# basic.net
KiCad netlist of a schematic drawn in EAGLE
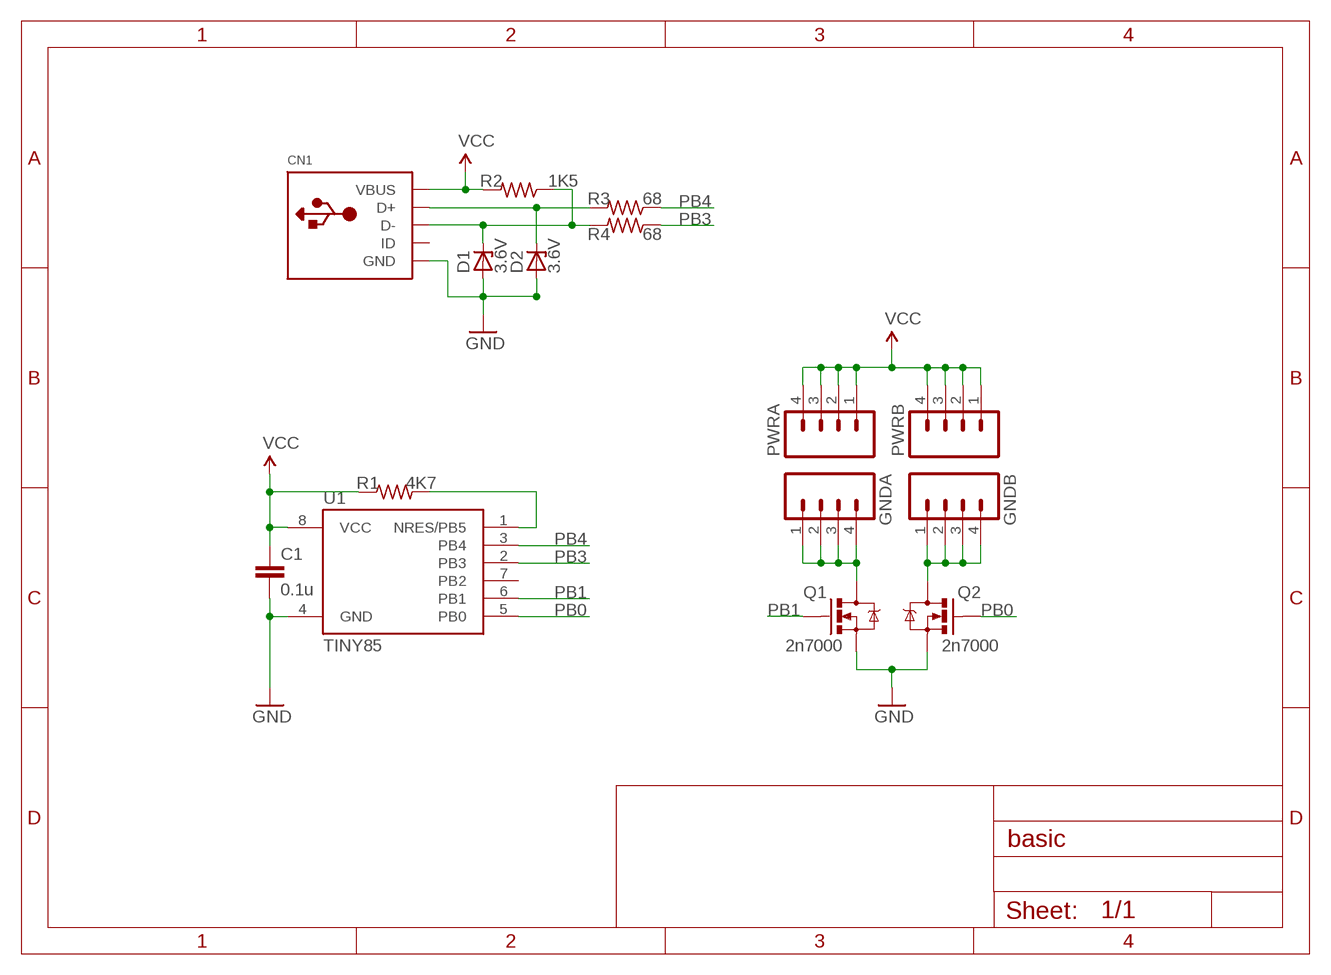
[diagram p0: schematic, sheet 1]

(export (version "E")
  (design (tool "Eeschema 10.0.6"))
  (components
    (comp (ref "C1")
      (value "0.1u")
      (footprint "eagle-import:C025-024X044")
      (libsource (lib "eagle-import") (part "C-EU025-024X044"))
    )
    (comp (ref "CN1")
      (value "USBMOLEX")
      (footprint "eagle-import:USB-MINIB-THM-MOLEX")
      (libsource (lib "eagle-import") (part "USBMOLEX"))
    )
    (comp (ref "D1")
      (value "3.6V")
      (footprint "eagle-import:ZDIO-5")
      (libsource (lib "eagle-import") (part "ZENER-DIODEZD-5"))
    )
    (comp (ref "D2")
      (value "3.6V")
      (footprint "eagle-import:ZDIO-5")
      (libsource (lib "eagle-import") (part "ZENER-DIODEZD-5"))
    )
    (comp (ref "GNDA")
      (value "M041X04_NO_SILK")
      (footprint "eagle-import:1X04_NO_SILK")
      (libsource (lib "eagle-import") (part "M041X04_NO_SILK"))
    )
    (comp (ref "GNDB")
      (value "M041X04_NO_SILK")
      (footprint "eagle-import:1X04_NO_SILK")
      (libsource (lib "eagle-import") (part "M041X04_NO_SILK"))
    )
    (comp (ref "PWRA")
      (value "M041X04_NO_SILK")
      (footprint "eagle-import:1X04_NO_SILK")
      (libsource (lib "eagle-import") (part "M041X04_NO_SILK"))
    )
    (comp (ref "PWRB")
      (value "M041X04_NO_SILK")
      (footprint "eagle-import:1X04_NO_SILK")
      (libsource (lib "eagle-import") (part "M041X04_NO_SILK"))
    )
    (comp (ref "Q1")
      (value "2n7000")
      (footprint "eagle-import:TO-92")
      (libsource (lib "eagle-import") (part "MOSFET-NCHANNEL2N7000"))
    )
    (comp (ref "Q2")
      (value "2n7000")
      (footprint "eagle-import:TO-92")
      (libsource (lib "eagle-import") (part "MOSFET-NCHANNEL2N7000"))
    )
    (comp (ref "R1")
      (value "4K7")
      (footprint "eagle-import:0204V")
      (libsource (lib "eagle-import") (part "R-US_0204/2V"))
    )
    (comp (ref "R2")
      (value "1K5")
      (footprint "eagle-import:0204V")
      (libsource (lib "eagle-import") (part "R-US_0204/2V"))
    )
    (comp (ref "R3")
      (value "68")
      (footprint "eagle-import:0204V")
      (libsource (lib "eagle-import") (part "R-US_0204/2V"))
    )
    (comp (ref "R4")
      (value "68")
      (footprint "eagle-import:0204V")
      (libsource (lib "eagle-import") (part "R-US_0204/2V"))
    )
    (comp (ref "U1")
      (value "TINY85")
      (footprint "eagle-import:PDIP08_300MIL")
      (libsource (lib "eagle-import") (part "ATTINY85P-20"))
    )
  )
  (nets
    (net (code "1") (name "/PB0") (class "Default")
      (node (ref "Q2") (pin "2") (pinfunction "G_2") (pintype "passive"))
      (node (ref "U1") (pin "5") (pinfunction "PB0_5") (pintype "bidirectional"))
    )
    (net (code "2") (name "/PB1") (class "Default")
      (node (ref "Q1") (pin "2") (pinfunction "G_2") (pintype "passive"))
      (node (ref "U1") (pin "6") (pinfunction "PB1_6") (pintype "bidirectional"))
    )
    (net (code "3") (name "/PB3") (class "Default")
      (node (ref "R4") (pin "1") (pinfunction "1_1") (pintype "passive"))
      (node (ref "U1") (pin "2") (pinfunction "PB3_2") (pintype "bidirectional"))
    )
    (net (code "4") (name "/PB4") (class "Default")
      (node (ref "R3") (pin "1") (pinfunction "1_1") (pintype "passive"))
      (node (ref "U1") (pin "3") (pinfunction "PB4_3") (pintype "bidirectional"))
    )
    (net (code "5") (name "GND") (class "Default")
      (node (ref "C1") (pin "2") (pinfunction "2_2") (pintype "passive"))
      (node (ref "CN1") (pin "GND") (pinfunction "GND_GND") (pintype "power_in"))
      (node (ref "D1") (pin "A") (pinfunction "A_A") (pintype "passive"))
      (node (ref "D2") (pin "A") (pinfunction "A_A") (pintype "passive"))
      (node (ref "Q1") (pin "1") (pinfunction "S_1") (pintype "passive"))
      (node (ref "Q2") (pin "1") (pinfunction "S_1") (pintype "passive"))
      (node (ref "U1") (pin "4") (pinfunction "GND_4") (pintype "power_in"))
    )
    (net (code "6") (name "Net-(CN1-PadD+)") (class "Default")
      (node (ref "CN1") (pin "D+") (pinfunction "D+_D+") (pintype "bidirectional"))
      (node (ref "D2") (pin "C") (pinfunction "C_C") (pintype "passive"))
      (node (ref "R3") (pin "2") (pinfunction "2_2") (pintype "passive"))
    )
    (net (code "7") (name "Net-(CN1-PadD-)") (class "Default")
      (node (ref "CN1") (pin "D-") (pinfunction "D-_D-") (pintype "bidirectional"))
      (node (ref "D1") (pin "C") (pinfunction "C_C") (pintype "passive"))
      (node (ref "R2") (pin "1") (pinfunction "1_1") (pintype "passive"))
      (node (ref "R4") (pin "2") (pinfunction "2_2") (pintype "passive"))
    )
    (net (code "8") (name "Net-(Q1-D)") (class "Default")
      (node (ref "GNDA") (pin "1") (pinfunction "1_1") (pintype "passive"))
      (node (ref "GNDA") (pin "2") (pinfunction "2_2") (pintype "passive"))
      (node (ref "GNDA") (pin "3") (pinfunction "3_3") (pintype "passive"))
      (node (ref "GNDA") (pin "4") (pinfunction "4_4") (pintype "passive"))
      (node (ref "Q1") (pin "3") (pinfunction "D_3") (pintype "passive"))
    )
    (net (code "9") (name "Net-(Q2-D)") (class "Default")
      (node (ref "GNDB") (pin "1") (pinfunction "1_1") (pintype "passive"))
      (node (ref "GNDB") (pin "2") (pinfunction "2_2") (pintype "passive"))
      (node (ref "GNDB") (pin "3") (pinfunction "3_3") (pintype "passive"))
      (node (ref "GNDB") (pin "4") (pinfunction "4_4") (pintype "passive"))
      (node (ref "Q2") (pin "3") (pinfunction "D_3") (pintype "passive"))
    )
    (net (code "10") (name "Net-(U1-NRES{slash}PB5)") (class "Default")
      (node (ref "R1") (pin "2") (pinfunction "2_2") (pintype "passive"))
      (node (ref "U1") (pin "1") (pinfunction "NRES/PB5_1") (pintype "bidirectional"))
    )
    (net (code "11") (name "VCC") (class "Default")
      (node (ref "C1") (pin "1") (pinfunction "1_1") (pintype "passive"))
      (node (ref "CN1") (pin "VBUS") (pinfunction "VBUS_VBUS") (pintype "power_in"))
      (node (ref "PWRA") (pin "1") (pinfunction "1_1") (pintype "passive"))
      (node (ref "PWRA") (pin "2") (pinfunction "2_2") (pintype "passive"))
      (node (ref "PWRA") (pin "3") (pinfunction "3_3") (pintype "passive"))
      (node (ref "PWRA") (pin "4") (pinfunction "4_4") (pintype "passive"))
      (node (ref "PWRB") (pin "1") (pinfunction "1_1") (pintype "passive"))
      (node (ref "PWRB") (pin "2") (pinfunction "2_2") (pintype "passive"))
      (node (ref "PWRB") (pin "3") (pinfunction "3_3") (pintype "passive"))
      (node (ref "PWRB") (pin "4") (pinfunction "4_4") (pintype "passive"))
      (node (ref "R1") (pin "1") (pinfunction "1_1") (pintype "passive"))
      (node (ref "R2") (pin "2") (pinfunction "2_2") (pintype "passive"))
      (node (ref "U1") (pin "8") (pinfunction "VCC_8") (pintype "power_in"))
    )
    (net (code "12") (name "unconnected-(CN1-PadID)") (class "Default")
      (node (ref "CN1") (pin "ID") (pinfunction "ID_ID") (pintype "bidirectional"))
    )
    (net (code "13") (name "unconnected-(U1-PB2-Pad7)") (class "Default")
      (node (ref "U1") (pin "7") (pinfunction "PB2_7") (pintype "bidirectional"))
    )
  )
)
